# Transmitter.net
KiCad netlist of a schematic drawn in Altium Designer
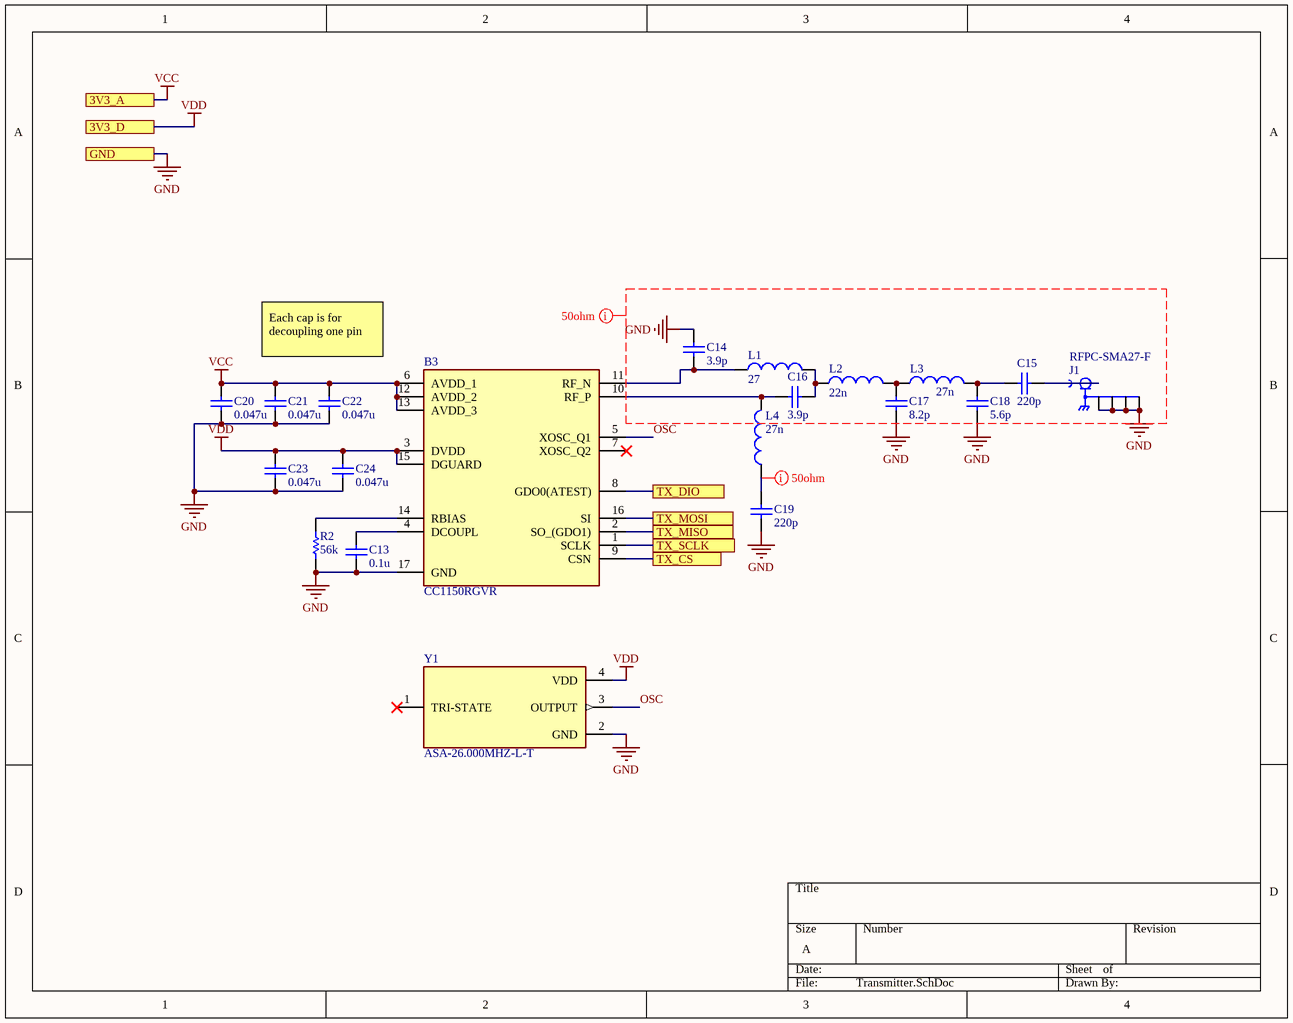
[diagram p0: Transmitter.SchDoc]

(export (version "E")
  (design (tool "Eeschema 10.0.6"))
  (components
    (comp (ref "B3")
      (value "CC1150RGVR")
      (footprint "QFN65P400X400X100-17N-D")
      (description "Highly Integrated Multichannel RF Transmitter Designed for Low-Power Wireless Applications")
      (fields (field (name "MOUSER PART NUMBER") "595-CC1150RGVR"))
      (libsource (lib "CC1150RGVR") (part "CC1150RGVR"))
    )
    (comp (ref "C13")
      (value "0.1u")
      (description "Capacitor")
      (libsource (lib "Simulation Generic Components") (part "Capacitor"))
    )
    (comp (ref "C14")
      (value "3.9p")
      (description "Capacitor")
      (libsource (lib "Simulation Generic Components") (part "Capacitor"))
    )
    (comp (ref "C15")
      (value "220p")
      (description "Capacitor")
      (libsource (lib "Simulation Generic Components") (part "Capacitor"))
    )
    (comp (ref "C16")
      (value "3.9p")
      (description "Capacitor")
      (libsource (lib "Simulation Generic Components") (part "Capacitor"))
    )
    (comp (ref "C17")
      (value "8.2p")
      (description "Capacitor")
      (libsource (lib "Simulation Generic Components") (part "Capacitor"))
    )
    (comp (ref "C18")
      (value "5.6p")
      (description "Capacitor")
      (libsource (lib "Simulation Generic Components") (part "Capacitor"))
    )
    (comp (ref "C19")
      (value "220p")
      (description "Capacitor")
      (libsource (lib "Simulation Generic Components") (part "Capacitor"))
    )
    (comp (ref "C20")
      (value "0.047u")
      (description "Capacitor")
      (libsource (lib "Simulation Generic Components") (part "Capacitor"))
    )
    (comp (ref "C21")
      (value "0.047u")
      (description "Capacitor")
      (libsource (lib "Simulation Generic Components") (part "Capacitor"))
    )
    (comp (ref "C22")
      (value "0.047u")
      (description "Capacitor")
      (libsource (lib "Simulation Generic Components") (part "Capacitor"))
    )
    (comp (ref "C23")
      (value "0.047u")
      (description "Capacitor")
      (libsource (lib "Simulation Generic Components") (part "Capacitor"))
    )
    (comp (ref "C24")
      (value "0.047u")
      (description "Capacitor")
      (libsource (lib "Simulation Generic Components") (part "Capacitor"))
    )
    (comp (ref "J1")
      (value "RFPC-SMA27-F")
      (footprint "GRADCONN_RFPC-SMA27-F")
      (fields (field (name "MF") "{'manufacturer': u'GCT (Gradconn)'}"))
      (libsource (lib "KeckWorkspace") (part "RFPC-SMA27-F"))
    )
    (comp (ref "L1")
      (value "27")
      (description "Inductor")
      (libsource (lib "Simulation Generic Components") (part "Inductor"))
    )
    (comp (ref "L2")
      (value "22n")
      (description "Inductor")
      (libsource (lib "Simulation Generic Components") (part "Inductor"))
    )
    (comp (ref "L3")
      (value "27n")
      (description "Inductor")
      (libsource (lib "Simulation Generic Components") (part "Inductor"))
    )
    (comp (ref "L4")
      (value "27n")
      (description "Inductor")
      (libsource (lib "Simulation Generic Components") (part "Inductor"))
    )
    (comp (ref "R2")
      (value "56k")
      (description "Resistor")
      (libsource (lib "Simulation Generic Components") (part "Resistor"))
    )
    (comp (ref "Y1")
      (value "ASA-26.000MHZ-L-T")
      (footprint "XTAL_ASA-26.000MHZ-L-T")
      (libsource (lib "KeckWorkspace") (part "ASA-26.000MHZ-L-T"))
    )
  )
  (nets
    (net (code "1") (name "/OSC") (class "Default")
      (node (ref "B3") (pin "5") (pinfunction "XOSC_Q1_5") (pintype "passive"))
      (node (ref "Y1") (pin "3") (pinfunction "OUTPUT_3") (pintype "output"))
    )
    (net (code "2") (name "/TX_CS") (class "Default")
      (node (ref "B3") (pin "9") (pinfunction "CSN_9") (pintype "passive"))
    )
    (net (code "3") (name "/TX_DIO") (class "Default")
      (node (ref "B3") (pin "8") (pinfunction "GDO0(ATEST)_8") (pintype "passive"))
    )
    (net (code "4") (name "/TX_MISO") (class "Default")
      (node (ref "B3") (pin "2") (pinfunction "SO_(GDO1)_2") (pintype "passive"))
    )
    (net (code "5") (name "/TX_MOSI") (class "Default")
      (node (ref "B3") (pin "16") (pinfunction "SI_16") (pintype "passive"))
    )
    (net (code "6") (name "/TX_SCLK") (class "Default")
      (node (ref "B3") (pin "1") (pinfunction "SCLK_1") (pintype "passive"))
    )
    (net (code "7") (name "GND") (class "Default")
      (node (ref "B3") (pin "17") (pinfunction "GND_17") (pintype "passive"))
      (node (ref "C13") (pin "1") (pinfunction "1_1") (pintype "passive"))
      (node (ref "C14") (pin "2") (pinfunction "2_2") (pintype "passive"))
      (node (ref "C17") (pin "1") (pinfunction "1_1") (pintype "passive"))
      (node (ref "C18") (pin "1") (pinfunction "1_1") (pintype "passive"))
      (node (ref "C19") (pin "1") (pinfunction "1_1") (pintype "passive"))
      (node (ref "C20") (pin "1") (pinfunction "1_1") (pintype "passive"))
      (node (ref "C21") (pin "1") (pinfunction "1_1") (pintype "passive"))
      (node (ref "C22") (pin "1") (pinfunction "1_1") (pintype "passive"))
      (node (ref "C23") (pin "1") (pinfunction "1_1") (pintype "passive"))
      (node (ref "C24") (pin "1") (pinfunction "1_1") (pintype "passive"))
      (node (ref "J1") (pin "G1") (pinfunction "G1_G1") (pintype "power_in"))
      (node (ref "J1") (pin "G2") (pinfunction "G2_G2") (pintype "power_in"))
      (node (ref "J1") (pin "G3") (pinfunction "G3_G3") (pintype "power_in"))
      (node (ref "J1") (pin "G4") (pinfunction "G4_G4") (pintype "power_in"))
      (node (ref "R2") (pin "1") (pinfunction "1_1") (pintype "passive"))
      (node (ref "Y1") (pin "2") (pinfunction "GND_2") (pintype "power_in"))
    )
    (net (code "8") (name "Net-(B3-DCOUPL)") (class "Default")
      (node (ref "B3") (pin "4") (pinfunction "DCOUPL_4") (pintype "passive"))
      (node (ref "C13") (pin "2") (pinfunction "2_2") (pintype "passive"))
    )
    (net (code "9") (name "Net-(B3-RBIAS)") (class "Default")
      (node (ref "B3") (pin "14") (pinfunction "RBIAS_14") (pintype "passive"))
      (node (ref "R2") (pin "2") (pinfunction "2_2") (pintype "passive"))
    )
    (net (code "10") (name "Net-(B3-RF_N)") (class "Default")
      (node (ref "B3") (pin "11") (pinfunction "RF_N_11") (pintype "passive"))
      (node (ref "C14") (pin "1") (pinfunction "1_1") (pintype "passive"))
      (node (ref "L1") (pin "1") (pinfunction "1_1") (pintype "passive"))
    )
    (net (code "11") (name "Net-(B3-RF_P)") (class "Default")
      (node (ref "B3") (pin "10") (pinfunction "RF_P_10") (pintype "passive"))
      (node (ref "C16") (pin "2") (pinfunction "2_2") (pintype "passive"))
      (node (ref "L4") (pin "2") (pinfunction "2_2") (pintype "passive"))
    )
    (net (code "12") (name "Net-(C15-Pad1)") (class "Default")
      (node (ref "C15") (pin "1") (pinfunction "1_1") (pintype "passive"))
      (node (ref "J1") (pin "1") (pinfunction "1_1") (pintype "passive"))
    )
    (net (code "13") (name "Net-(C15-Pad2)") (class "Default")
      (node (ref "C15") (pin "2") (pinfunction "2_2") (pintype "passive"))
      (node (ref "C18") (pin "2") (pinfunction "2_2") (pintype "passive"))
      (node (ref "L3") (pin "2") (pinfunction "2_2") (pintype "passive"))
    )
    (net (code "14") (name "Net-(C16-Pad1)") (class "Default")
      (node (ref "C16") (pin "1") (pinfunction "1_1") (pintype "passive"))
      (node (ref "L1") (pin "2") (pinfunction "2_2") (pintype "passive"))
      (node (ref "L2") (pin "1") (pinfunction "1_1") (pintype "passive"))
    )
    (net (code "15") (name "Net-(C17-Pad2)") (class "Default")
      (node (ref "C17") (pin "2") (pinfunction "2_2") (pintype "passive"))
      (node (ref "L2") (pin "2") (pinfunction "2_2") (pintype "passive"))
      (node (ref "L3") (pin "1") (pinfunction "1_1") (pintype "passive"))
    )
    (net (code "16") (name "Net-(C19-Pad2)") (class "Default")
      (node (ref "C19") (pin "2") (pinfunction "2_2") (pintype "passive"))
      (node (ref "L4") (pin "1") (pinfunction "1_1") (pintype "passive"))
    )
    (net (code "17") (name "VCC") (class "Default")
      (node (ref "B3") (pin "12") (pinfunction "AVDD_2_12") (pintype "passive"))
      (node (ref "B3") (pin "13") (pinfunction "AVDD_3_13") (pintype "passive"))
      (node (ref "B3") (pin "6") (pinfunction "AVDD_1_6") (pintype "passive"))
      (node (ref "C20") (pin "2") (pinfunction "2_2") (pintype "passive"))
      (node (ref "C21") (pin "2") (pinfunction "2_2") (pintype "passive"))
      (node (ref "C22") (pin "2") (pinfunction "2_2") (pintype "passive"))
    )
    (net (code "18") (name "VDD") (class "Default")
      (node (ref "B3") (pin "15") (pinfunction "DGUARD_15") (pintype "passive"))
      (node (ref "B3") (pin "3") (pinfunction "DVDD_3") (pintype "passive"))
      (node (ref "C23") (pin "2") (pinfunction "2_2") (pintype "passive"))
      (node (ref "C24") (pin "2") (pinfunction "2_2") (pintype "passive"))
      (node (ref "Y1") (pin "4") (pinfunction "VDD_4") (pintype "power_in"))
    )
    (net (code "19") (name "unconnected-(B3-XOSC_Q2-Pad7)") (class "Default")
      (node (ref "B3") (pin "7") (pinfunction "XOSC_Q2_7") (pintype "passive+no_connect"))
    )
    (net (code "20") (name "unconnected-(Y1-TRI-STATE-Pad1)") (class "Default")
      (node (ref "Y1") (pin "1") (pinfunction "TRI-STATE_1") (pintype "passive+no_connect"))
    )
  )
)
